# nearsens-schematic-source-2026-05-26-dra.net
KiCad netlist of a schematic drawn in EasyEDA
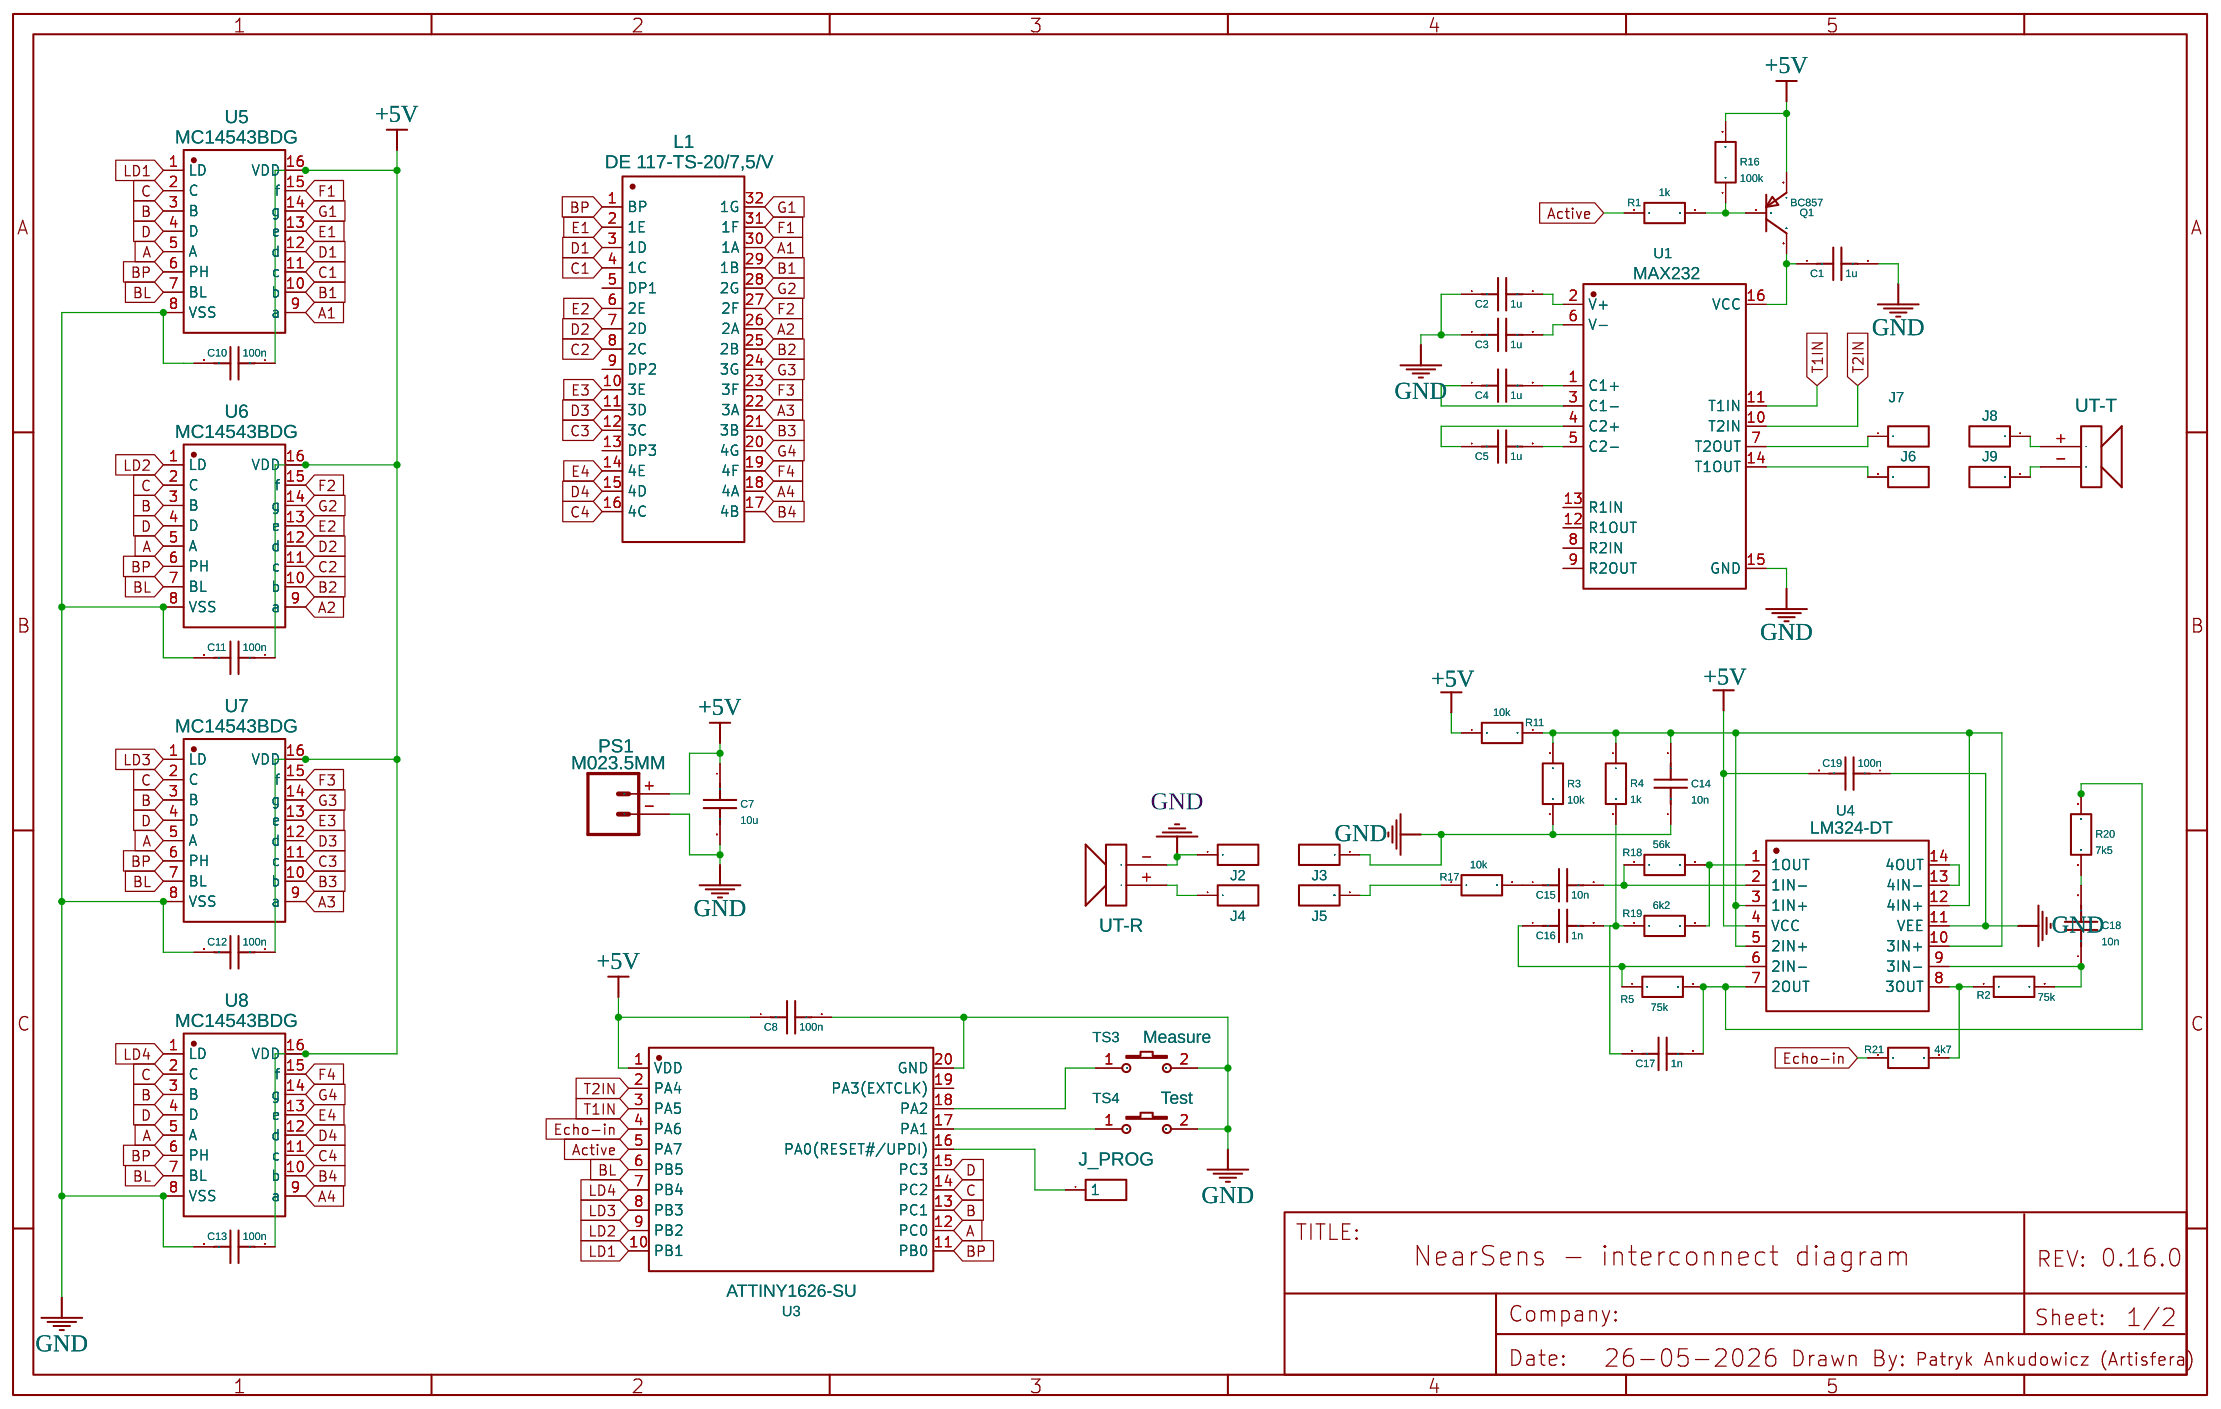
[diagram p0: schematic sheet]

(export (version "E")
  (design (tool "Eeschema 10.0.6"))
  (components
    (comp (ref "C1") (value "1u") (libsource (lib "") (part "C_0603_US")))
    (comp (ref "C2") (value "1u") (libsource (lib "") (part "C_0603_US")))
    (comp (ref "C3") (value "1u") (libsource (lib "") (part "C_0603_US")))
    (comp (ref "C4") (value "1u") (libsource (lib "") (part "C_0603_US")))
    (comp (ref "C5") (value "1u") (libsource (lib "") (part "C_0603_US")))
    (comp (ref "C7") (value "10u") (libsource (lib "") (part "C_0603_US_2")))
    (comp (ref "C8") (value "100n") (libsource (lib "") (part "C_0603_US")))
    (comp (ref "C10") (value "100n") (libsource (lib "") (part "C_0603_US_3")))
    (comp (ref "C11") (value "100n") (libsource (lib "") (part "C_0603_US_3")))
    (comp (ref "C12") (value "100n") (libsource (lib "") (part "C_0603_US_3")))
    (comp (ref "C13") (value "100n") (libsource (lib "") (part "C_0603_US_3")))
    (comp (ref "C14") (value "10n") (libsource (lib "") (part "C_0603_US_1")))
    (comp (ref "C15") (value "10n") (libsource (lib "") (part "C_0603_US")))
    (comp (ref "C16") (value "1n") (libsource (lib "") (part "C_0603_US")))
    (comp (ref "C17") (value "1n") (libsource (lib "") (part "C_0603_US")))
    (comp (ref "C18") (value "10n") (libsource (lib "") (part "C_0603_US_1")))
    (comp (ref "C19") (value "100n") (libsource (lib "") (part "C_0603_US_3")))
    (comp (ref "J2") (value "HDR-M-2.54_1x1") (libsource (lib "") (part "HDR-M-2.54_1x1_1")))
    (comp (ref "J3") (value "HDR-M-2.54_1x1") (libsource (lib "") (part "HDR-M-2.54_1x1")))
    (comp (ref "J4") (value "HDR-M-2.54_1x1") (libsource (lib "") (part "HDR-M-2.54_1x1_1")))
    (comp (ref "J5") (value "HDR-M-2.54_1x1") (libsource (lib "") (part "HDR-M-2.54_1x1_3")))
    (comp (ref "J6") (value "HDR-M-2.54_1x1") (libsource (lib "") (part "HDR-M-2.54_1x1_1")))
    (comp (ref "J7") (value "HDR-M-2.54_1x1") (libsource (lib "") (part "HDR-M-2.54_1x1_1")))
    (comp (ref "J8") (value "HDR-M-2.54_1x1") (libsource (lib "") (part "HDR-M-2.54_1x1")))
    (comp (ref "J9") (value "HDR-M-2.54_1x1") (libsource (lib "") (part "HDR-M-2.54_1x1")))
    (comp (ref "J_PROG") (value "Programming") (libsource (lib "") (part "HDR-M-2.54_1x1_2")))
    (comp (ref "L1")
      (value "DE 117-TS-20/7,5/V")
      (fields (field (name "Manufacturer") "DISPLAY ELEKTRONIK"))
      (libsource (lib "") (part "DE 117-TS-20/7,5/V DISPLAY ELEKTRONIK - Display LCD"))
    )
    (comp (ref "PS1") (value "M023.5MM") (libsource (lib "") (part "M023.5MM")))
    (comp (ref "Q1")
      (value "BC857")
      (fields
        (field (name "Manufacturer Part") "BC557(RANGE:420-800)")
        (field (name "Manufacturer") "CJ(江苏长电/长晶)")
      )
      (libsource (lib "") (part "BC557"))
    )
    (comp (ref "R1") (value "1k") (libsource (lib "") (part "R_0603_EU_1")))
    (comp (ref "R2") (value "75k") (libsource (lib "") (part "R_0603_EU_1")))
    (comp (ref "R3") (value "10k") (libsource (lib "") (part "R_0603_EU")))
    (comp (ref "R4") (value "1k") (libsource (lib "") (part "R_0603_EU_2")))
    (comp (ref "R5") (value "75k") (libsource (lib "") (part "R_0603_EU_1")))
    (comp (ref "R11") (value "10k") (libsource (lib "") (part "R_0603_EU_1")))
    (comp (ref "R16") (value "100k") (libsource (lib "") (part "R_0603_EU")))
    (comp (ref "R17") (value "10k") (libsource (lib "") (part "R_0603_EU_1")))
    (comp (ref "R18") (value "56k") (libsource (lib "") (part "R_0603_EU_1")))
    (comp (ref "R19") (value "6k2") (libsource (lib "") (part "R_0603_EU_1")))
    (comp (ref "R20") (value "7k5") (libsource (lib "") (part "R_0603_EU")))
    (comp (ref "R21") (value "4k7") (libsource (lib "") (part "R_0603_EU_1")))
    (comp (ref "TS3")
      (value "Measure")
      (fields (field (name "Manufacturer Part") "K2-1107ST-A4SW-06"))
      (libsource (lib "") (part "K2-3.6×6.1_SMD"))
    )
    (comp (ref "TS4")
      (value "Test")
      (fields (field (name "Manufacturer Part") "K2-1107ST-A4SW-06"))
      (libsource (lib "") (part "K2-3.6×6.1_SMD"))
    )
    (comp (ref "U1")
      (value "MAX232")
      (fields (field (name "Manufacturer Part") "MAX232ESE-EV") (field (name "Manufacturer") "EVVO(翊欧)"))
      (libsource (lib "") (part "MAX232ESE-EV"))
    )
    (comp (ref "U3")
      (value "ATTINY1626-SU")
      (fields (field (name "Manufacturer") "MICROCHIP(美国微芯)"))
      (libsource (lib "") (part "ATTINY1626-SU"))
    )
    (comp (ref "U4")
      (value "LM324-DT")
      (fields (field (name "Manufacturer Part") "LM324-DW") (field (name "Manufacturer") "DOWO(东沃)"))
      (libsource (lib "") (part "LM324-DW"))
    )
    (comp (ref "U5") (value "MC14543BDG") (libsource (lib "") (part "MC14543BDG")))
    (comp (ref "U6") (value "MC14543BDG") (libsource (lib "") (part "MC14543BDG")))
    (comp (ref "U7") (value "MC14543BDG") (libsource (lib "") (part "MC14543BDG")))
    (comp (ref "U8") (value "MC14543BDG") (libsource (lib "") (part "MC14543BDG")))
    (comp (ref "UT-R")
      (value "Przetwornik ultradzwiekowy")
      (fields (field (name "Manufacturer Part") "I47123") (field (name "Manufacturer") "I47"))
      (libsource (lib "") (part "ULTRASONIC TRANSDUCER_1"))
    )
    (comp (ref "UT-T")
      (value "Przetwornik ultradzwiekowy")
      (fields (field (name "Manufacturer Part") "I47123") (field (name "Manufacturer") "I47"))
      (libsource (lib "") (part "ULTRASONIC TRANSDUCER"))
    )
  )
  (nets
    (net (code "1") (name "+5V") (class "Default")
      (node (ref "C10") (pin "1") (pinfunction "1_1") (pintype "unspecified"))
      (node (ref "C11") (pin "1") (pinfunction "1_1") (pintype "unspecified"))
      (node (ref "C12") (pin "1") (pinfunction "1_1") (pintype "unspecified"))
      (node (ref "C13") (pin "1") (pinfunction "1_1") (pintype "unspecified"))
      (node (ref "C19") (pin "2") (pinfunction "2_2") (pintype "unspecified"))
      (node (ref "C7") (pin "1") (pinfunction "1_1") (pintype "unspecified"))
      (node (ref "C8") (pin "1") (pinfunction "1_1") (pintype "unspecified"))
      (node (ref "PS1") (pin "+") (pinfunction "2_+") (pintype "bidirectional"))
      (node (ref "Q1") (pin "2") (pinfunction "E_2") (pintype "unspecified"))
      (node (ref "R11") (pin "1") (pinfunction "1_1") (pintype "unspecified"))
      (node (ref "R16") (pin "2") (pinfunction "2_2") (pintype "unspecified"))
      (node (ref "U3") (pin "1") (pinfunction "VDD_1") (pintype "unspecified"))
      (node (ref "U4") (pin "4") (pinfunction "VCC_4") (pintype "unspecified"))
      (node (ref "U5") (pin "16") (pinfunction "VDD_16") (pintype "unspecified"))
      (node (ref "U6") (pin "16") (pinfunction "VDD_16") (pintype "unspecified"))
      (node (ref "U7") (pin "16") (pinfunction "VDD_16") (pintype "unspecified"))
      (node (ref "U8") (pin "16") (pinfunction "VDD_16") (pintype "unspecified"))
    )
    (net (code "2") (name "A") (class "Default")
      (node (ref "U3") (pin "12") (pinfunction "PC0_12") (pintype "unspecified"))
      (node (ref "U5") (pin "5") (pinfunction "A_5") (pintype "unspecified"))
      (node (ref "U6") (pin "5") (pinfunction "A_5") (pintype "unspecified"))
      (node (ref "U7") (pin "5") (pinfunction "A_5") (pintype "unspecified"))
      (node (ref "U8") (pin "5") (pinfunction "A_5") (pintype "unspecified"))
    )
    (net (code "3") (name "A1") (class "Default")
      (node (ref "L1") (pin "30") (pinfunction "1A_30") (pintype "unspecified"))
      (node (ref "U5") (pin "9") (pinfunction "a_9") (pintype "unspecified"))
    )
    (net (code "4") (name "A2") (class "Default")
      (node (ref "L1") (pin "26") (pinfunction "2A_26") (pintype "unspecified"))
      (node (ref "U6") (pin "9") (pinfunction "a_9") (pintype "unspecified"))
    )
    (net (code "5") (name "A3") (class "Default")
      (node (ref "L1") (pin "22") (pinfunction "3A_22") (pintype "unspecified"))
      (node (ref "U7") (pin "9") (pinfunction "a_9") (pintype "unspecified"))
    )
    (net (code "6") (name "A4") (class "Default")
      (node (ref "L1") (pin "18") (pinfunction "4A_18") (pintype "unspecified"))
      (node (ref "U8") (pin "9") (pinfunction "a_9") (pintype "unspecified"))
    )
    (net (code "7") (name "Active") (class "Default")
      (node (ref "R1") (pin "1") (pinfunction "1_1") (pintype "unspecified"))
      (node (ref "U3") (pin "5") (pinfunction "PA7_5") (pintype "unspecified"))
    )
    (net (code "8") (name "B") (class "Default")
      (node (ref "U3") (pin "13") (pinfunction "PC1_13") (pintype "unspecified"))
      (node (ref "U5") (pin "3") (pinfunction "B_3") (pintype "unspecified"))
      (node (ref "U6") (pin "3") (pinfunction "B_3") (pintype "unspecified"))
      (node (ref "U7") (pin "3") (pinfunction "B_3") (pintype "unspecified"))
      (node (ref "U8") (pin "3") (pinfunction "B_3") (pintype "unspecified"))
    )
    (net (code "9") (name "B1") (class "Default")
      (node (ref "L1") (pin "29") (pinfunction "1B_29") (pintype "unspecified"))
      (node (ref "U5") (pin "10") (pinfunction "b_10") (pintype "unspecified"))
    )
    (net (code "10") (name "B2") (class "Default")
      (node (ref "L1") (pin "25") (pinfunction "2B_25") (pintype "unspecified"))
      (node (ref "U6") (pin "10") (pinfunction "b_10") (pintype "unspecified"))
    )
    (net (code "11") (name "B3") (class "Default")
      (node (ref "L1") (pin "21") (pinfunction "3B_21") (pintype "unspecified"))
      (node (ref "U7") (pin "10") (pinfunction "b_10") (pintype "unspecified"))
    )
    (net (code "12") (name "B4") (class "Default")
      (node (ref "L1") (pin "17") (pinfunction "4B_17") (pintype "unspecified"))
      (node (ref "U8") (pin "10") (pinfunction "b_10") (pintype "unspecified"))
    )
    (net (code "13") (name "BL") (class "Default")
      (node (ref "U3") (pin "6") (pinfunction "PB5_6") (pintype "unspecified"))
      (node (ref "U5") (pin "7") (pinfunction "BL_7") (pintype "unspecified"))
      (node (ref "U6") (pin "7") (pinfunction "BL_7") (pintype "unspecified"))
      (node (ref "U7") (pin "7") (pinfunction "BL_7") (pintype "unspecified"))
      (node (ref "U8") (pin "7") (pinfunction "BL_7") (pintype "unspecified"))
    )
    (net (code "14") (name "BP") (class "Default")
      (node (ref "L1") (pin "1") (pinfunction "BP_1") (pintype "unspecified"))
      (node (ref "U3") (pin "11") (pinfunction "PB0_11") (pintype "unspecified"))
      (node (ref "U5") (pin "6") (pinfunction "PH_6") (pintype "unspecified"))
      (node (ref "U6") (pin "6") (pinfunction "PH_6") (pintype "unspecified"))
      (node (ref "U7") (pin "6") (pinfunction "PH_6") (pintype "unspecified"))
      (node (ref "U8") (pin "6") (pinfunction "PH_6") (pintype "unspecified"))
    )
    (net (code "15") (name "C") (class "Default")
      (node (ref "U3") (pin "14") (pinfunction "PC2_14") (pintype "unspecified"))
      (node (ref "U5") (pin "2") (pinfunction "C_2") (pintype "unspecified"))
      (node (ref "U6") (pin "2") (pinfunction "C_2") (pintype "unspecified"))
      (node (ref "U7") (pin "2") (pinfunction "C_2") (pintype "unspecified"))
      (node (ref "U8") (pin "2") (pinfunction "C_2") (pintype "unspecified"))
    )
    (net (code "16") (name "C1") (class "Default")
      (node (ref "L1") (pin "4") (pinfunction "1C_4") (pintype "unspecified"))
      (node (ref "U5") (pin "11") (pinfunction "c_11") (pintype "unspecified"))
    )
    (net (code "17") (name "C2") (class "Default")
      (node (ref "L1") (pin "8") (pinfunction "2C_8") (pintype "unspecified"))
      (node (ref "U6") (pin "11") (pinfunction "c_11") (pintype "unspecified"))
    )
    (net (code "18") (name "C3") (class "Default")
      (node (ref "L1") (pin "12") (pinfunction "3C_12") (pintype "unspecified"))
      (node (ref "U7") (pin "11") (pinfunction "c_11") (pintype "unspecified"))
    )
    (net (code "19") (name "C4") (class "Default")
      (node (ref "L1") (pin "16") (pinfunction "4C_16") (pintype "unspecified"))
      (node (ref "U8") (pin "11") (pinfunction "c_11") (pintype "unspecified"))
    )
    (net (code "20") (name "D") (class "Default")
      (node (ref "U3") (pin "15") (pinfunction "PC3_15") (pintype "unspecified"))
      (node (ref "U5") (pin "4") (pinfunction "D_4") (pintype "unspecified"))
      (node (ref "U6") (pin "4") (pinfunction "D_4") (pintype "unspecified"))
      (node (ref "U7") (pin "4") (pinfunction "D_4") (pintype "unspecified"))
      (node (ref "U8") (pin "4") (pinfunction "D_4") (pintype "unspecified"))
    )
    (net (code "21") (name "D1") (class "Default")
      (node (ref "L1") (pin "3") (pinfunction "1D_3") (pintype "unspecified"))
      (node (ref "U5") (pin "12") (pinfunction "d_12") (pintype "unspecified"))
    )
    (net (code "22") (name "D2") (class "Default")
      (node (ref "L1") (pin "7") (pinfunction "2D_7") (pintype "unspecified"))
      (node (ref "U6") (pin "12") (pinfunction "d_12") (pintype "unspecified"))
    )
    (net (code "23") (name "D3") (class "Default")
      (node (ref "L1") (pin "11") (pinfunction "3D_11") (pintype "unspecified"))
      (node (ref "U7") (pin "12") (pinfunction "d_12") (pintype "unspecified"))
    )
    (net (code "24") (name "D4") (class "Default")
      (node (ref "L1") (pin "15") (pinfunction "4D_15") (pintype "unspecified"))
      (node (ref "U8") (pin "12") (pinfunction "d_12") (pintype "unspecified"))
    )
    (net (code "25") (name "E1") (class "Default")
      (node (ref "L1") (pin "2") (pinfunction "1E_2") (pintype "unspecified"))
      (node (ref "U5") (pin "13") (pinfunction "e_13") (pintype "unspecified"))
    )
    (net (code "26") (name "E2") (class "Default")
      (node (ref "L1") (pin "6") (pinfunction "2E_6") (pintype "unspecified"))
      (node (ref "U6") (pin "13") (pinfunction "e_13") (pintype "unspecified"))
    )
    (net (code "27") (name "E3") (class "Default")
      (node (ref "L1") (pin "10") (pinfunction "3E_10") (pintype "unspecified"))
      (node (ref "U7") (pin "13") (pinfunction "e_13") (pintype "unspecified"))
    )
    (net (code "28") (name "E4") (class "Default")
      (node (ref "L1") (pin "14") (pinfunction "4E_14") (pintype "unspecified"))
      (node (ref "U8") (pin "13") (pinfunction "e_13") (pintype "unspecified"))
    )
    (net (code "29") (name "Echo-in") (class "Default")
      (node (ref "R21") (pin "1") (pinfunction "1_1") (pintype "unspecified"))
      (node (ref "U3") (pin "4") (pinfunction "PA6_4") (pintype "unspecified"))
    )
    (net (code "30") (name "F1") (class "Default")
      (node (ref "L1") (pin "31") (pinfunction "1F_31") (pintype "unspecified"))
      (node (ref "U5") (pin "15") (pinfunction "f_15") (pintype "unspecified"))
    )
    (net (code "31") (name "F2") (class "Default")
      (node (ref "L1") (pin "27") (pinfunction "2F_27") (pintype "unspecified"))
      (node (ref "U6") (pin "15") (pinfunction "f_15") (pintype "unspecified"))
    )
    (net (code "32") (name "F3") (class "Default")
      (node (ref "L1") (pin "23") (pinfunction "3F_23") (pintype "unspecified"))
      (node (ref "U7") (pin "15") (pinfunction "f_15") (pintype "unspecified"))
    )
    (net (code "33") (name "F4") (class "Default")
      (node (ref "L1") (pin "19") (pinfunction "4F_19") (pintype "unspecified"))
      (node (ref "U8") (pin "15") (pinfunction "f_15") (pintype "unspecified"))
    )
    (net (code "34") (name "G1") (class "Default")
      (node (ref "L1") (pin "32") (pinfunction "1G_32") (pintype "unspecified"))
      (node (ref "U5") (pin "14") (pinfunction "g_14") (pintype "unspecified"))
    )
    (net (code "35") (name "G2") (class "Default")
      (node (ref "L1") (pin "28") (pinfunction "2G_28") (pintype "unspecified"))
      (node (ref "U6") (pin "14") (pinfunction "g_14") (pintype "unspecified"))
    )
    (net (code "36") (name "G3") (class "Default")
      (node (ref "L1") (pin "24") (pinfunction "3G_24") (pintype "unspecified"))
      (node (ref "U7") (pin "14") (pinfunction "g_14") (pintype "unspecified"))
    )
    (net (code "37") (name "G4") (class "Default")
      (node (ref "L1") (pin "20") (pinfunction "4G_20") (pintype "unspecified"))
      (node (ref "U8") (pin "14") (pinfunction "g_14") (pintype "unspecified"))
    )
    (net (code "38") (name "GND") (class "Default")
      (node (ref "C1") (pin "2") (pinfunction "2_2") (pintype "unspecified"))
      (node (ref "C10") (pin "2") (pinfunction "2_2") (pintype "unspecified"))
      (node (ref "C11") (pin "2") (pinfunction "2_2") (pintype "unspecified"))
      (node (ref "C12") (pin "2") (pinfunction "2_2") (pintype "unspecified"))
      (node (ref "C13") (pin "2") (pinfunction "2_2") (pintype "unspecified"))
      (node (ref "C14") (pin "1") (pinfunction "1_1") (pintype "unspecified"))
      (node (ref "C19") (pin "1") (pinfunction "1_1") (pintype "unspecified"))
      (node (ref "C2") (pin "1") (pinfunction "1_1") (pintype "unspecified"))
      (node (ref "C3") (pin "1") (pinfunction "1_1") (pintype "unspecified"))
      (node (ref "C7") (pin "2") (pinfunction "2_2") (pintype "unspecified"))
      (node (ref "C8") (pin "2") (pinfunction "2_2") (pintype "unspecified"))
      (node (ref "J2") (pin "1") (pinfunction "1_1") (pintype "input"))
      (node (ref "J3") (pin "1") (pinfunction "1_1") (pintype "input"))
      (node (ref "PS1") (pin "-") (pinfunction "1_-") (pintype "bidirectional"))
      (node (ref "R3") (pin "1") (pinfunction "1_1") (pintype "unspecified"))
      (node (ref "TS3") (pin "2") (pinfunction "2_2") (pintype "unspecified"))
      (node (ref "TS4") (pin "2") (pinfunction "2_2") (pintype "unspecified"))
      (node (ref "U1") (pin "15") (pinfunction "GND_15") (pintype "unspecified"))
      (node (ref "U3") (pin "20") (pinfunction "GND_20") (pintype "unspecified"))
      (node (ref "U4") (pin "11") (pinfunction "VEE_11") (pintype "unspecified"))
      (node (ref "U5") (pin "8") (pinfunction "VSS_8") (pintype "unspecified"))
      (node (ref "U6") (pin "8") (pinfunction "VSS_8") (pintype "unspecified"))
      (node (ref "U7") (pin "8") (pinfunction "VSS_8") (pintype "unspecified"))
      (node (ref "U8") (pin "8") (pinfunction "VSS_8") (pintype "unspecified"))
      (node (ref "UT-R") (pin "-") (pinfunction "+_-") (pintype "bidirectional"))
    )
    (net (code "39") (name "LD1") (class "Default")
      (node (ref "U3") (pin "10") (pinfunction "PB1_10") (pintype "unspecified"))
      (node (ref "U5") (pin "1") (pinfunction "LD_1") (pintype "unspecified"))
    )
    (net (code "40") (name "LD2") (class "Default")
      (node (ref "U3") (pin "9") (pinfunction "PB2_9") (pintype "unspecified"))
      (node (ref "U6") (pin "1") (pinfunction "LD_1") (pintype "unspecified"))
    )
    (net (code "41") (name "LD3") (class "Default")
      (node (ref "U3") (pin "8") (pinfunction "PB3_8") (pintype "unspecified"))
      (node (ref "U7") (pin "1") (pinfunction "LD_1") (pintype "unspecified"))
    )
    (net (code "42") (name "LD4") (class "Default")
      (node (ref "U3") (pin "7") (pinfunction "PB4_7") (pintype "unspecified"))
      (node (ref "U8") (pin "1") (pinfunction "LD_1") (pintype "unspecified"))
    )
    (net (code "43") (name "Net-(C15-Pad1)") (class "Default")
      (node (ref "C15") (pin "1") (pinfunction "1_1") (pintype "unspecified"))
      (node (ref "R17") (pin "2") (pinfunction "2_2") (pintype "unspecified"))
    )
    (net (code "44") (name "Net-(C16-Pad2)") (class "Default")
      (node (ref "C16") (pin "2") (pinfunction "2_2") (pintype "unspecified"))
      (node (ref "C17") (pin "1") (pinfunction "1_1") (pintype "unspecified"))
      (node (ref "R19") (pin "1") (pinfunction "1_1") (pintype "unspecified"))
      (node (ref "R4") (pin "2") (pinfunction "2_2") (pintype "unspecified"))
    )
    (net (code "45") (name "Net-(C18-Pad2)") (class "Default")
      (node (ref "C18") (pin "2") (pinfunction "2_2") (pintype "unspecified"))
      (node (ref "R20") (pin "1") (pinfunction "1_1") (pintype "unspecified"))
    )
    (net (code "46") (name "Net-(J5-PAD)") (class "Default")
      (node (ref "J5") (pin "1") (pinfunction "PAD_1") (pintype "input"))
      (node (ref "R17") (pin "1") (pinfunction "1_1") (pintype "unspecified"))
    )
    (net (code "47") (name "Net-(Q1-B)") (class "Default")
      (node (ref "Q1") (pin "1") (pinfunction "B_1") (pintype "unspecified"))
      (node (ref "R1") (pin "2") (pinfunction "2_2") (pintype "unspecified"))
      (node (ref "R16") (pin "1") (pinfunction "1_1") (pintype "unspecified"))
    )
    (net (code "48") (name "Net-(Q1-C)") (class "Default")
      (node (ref "C1") (pin "1") (pinfunction "1_1") (pintype "unspecified"))
      (node (ref "Q1") (pin "3") (pinfunction "C_3") (pintype "unspecified"))
      (node (ref "U1") (pin "16") (pinfunction "VCC_16") (pintype "unspecified"))
    )
    (net (code "49") (name "Net-(U1-C1+)") (class "Default")
      (node (ref "C4") (pin "2") (pinfunction "2_2") (pintype "unspecified"))
      (node (ref "U1") (pin "1") (pinfunction "C1+_1") (pintype "unspecified"))
    )
    (net (code "50") (name "Net-(U1-C1-)") (class "Default")
      (node (ref "C4") (pin "1") (pinfunction "1_1") (pintype "unspecified"))
      (node (ref "U1") (pin "3") (pinfunction "C1-_3") (pintype "unspecified"))
    )
    (net (code "51") (name "Net-(U1-C2+)") (class "Default")
      (node (ref "C5") (pin "1") (pinfunction "1_1") (pintype "unspecified"))
      (node (ref "U1") (pin "4") (pinfunction "C2+_4") (pintype "unspecified"))
    )
    (net (code "52") (name "Net-(U1-C2-)") (class "Default")
      (node (ref "C5") (pin "2") (pinfunction "2_2") (pintype "unspecified"))
      (node (ref "U1") (pin "5") (pinfunction "C2-_5") (pintype "unspecified"))
    )
    (net (code "53") (name "Net-(U1-T1OUT)") (class "Default")
      (node (ref "J6") (pin "1") (pinfunction "1_1") (pintype "input"))
      (node (ref "U1") (pin "14") (pinfunction "T1OUT_14") (pintype "unspecified"))
    )
    (net (code "54") (name "Net-(U1-T2OUT)") (class "Default")
      (node (ref "J7") (pin "1") (pinfunction "1_1") (pintype "input"))
      (node (ref "U1") (pin "7") (pinfunction "T2OUT_7") (pintype "unspecified"))
    )
    (net (code "55") (name "Net-(U1-V+)") (class "Default")
      (node (ref "C2") (pin "2") (pinfunction "2_2") (pintype "unspecified"))
      (node (ref "U1") (pin "2") (pinfunction "V+_2") (pintype "unspecified"))
    )
    (net (code "56") (name "Net-(U1-V-)") (class "Default")
      (node (ref "C3") (pin "2") (pinfunction "2_2") (pintype "unspecified"))
      (node (ref "U1") (pin "6") (pinfunction "V-_6") (pintype "unspecified"))
    )
    (net (code "57") (name "Net-(U3-PA0(RESET#{slash}UPDI))") (class "Default")
      (node (ref "J_PROG") (pin "1") (pinfunction "1_1") (pintype "input"))
      (node (ref "U3") (pin "16") (pinfunction "PA0(RESET#/UPDI)_16") (pintype "unspecified"))
    )
    (net (code "58") (name "Net-(U3-PA1)") (class "Default")
      (node (ref "TS4") (pin "1") (pinfunction "1_1") (pintype "unspecified"))
      (node (ref "U3") (pin "17") (pinfunction "PA1_17") (pintype "unspecified"))
    )
    (net (code "59") (name "Net-(U3-PA2)") (class "Default")
      (node (ref "TS3") (pin "1") (pinfunction "1_1") (pintype "unspecified"))
      (node (ref "U3") (pin "18") (pinfunction "PA2_18") (pintype "unspecified"))
    )
    (net (code "60") (name "Net-(U4-1IN+)") (class "Default")
      (node (ref "C14") (pin "2") (pinfunction "2_2") (pintype "unspecified"))
      (node (ref "R11") (pin "2") (pinfunction "2_2") (pintype "unspecified"))
      (node (ref "R3") (pin "2") (pinfunction "2_2") (pintype "unspecified"))
      (node (ref "R4") (pin "1") (pinfunction "1_1") (pintype "unspecified"))
      (node (ref "U4") (pin "10") (pinfunction "3IN+_10") (pintype "unspecified"))
      (node (ref "U4") (pin "12") (pinfunction "4IN+_12") (pintype "unspecified"))
      (node (ref "U4") (pin "3") (pinfunction "1IN+_3") (pintype "unspecified"))
      (node (ref "U4") (pin "5") (pinfunction "2IN+_5") (pintype "unspecified"))
    )
    (net (code "61") (name "Net-(U4-1IN-)") (class "Default")
      (node (ref "C15") (pin "2") (pinfunction "2_2") (pintype "unspecified"))
      (node (ref "R18") (pin "1") (pinfunction "1_1") (pintype "unspecified"))
      (node (ref "U4") (pin "2") (pinfunction "1IN-_2") (pintype "unspecified"))
    )
    (net (code "62") (name "Net-(U4-1OUT)") (class "Default")
      (node (ref "R18") (pin "2") (pinfunction "2_2") (pintype "unspecified"))
      (node (ref "R19") (pin "2") (pinfunction "2_2") (pintype "unspecified"))
      (node (ref "U4") (pin "1") (pinfunction "1OUT_1") (pintype "unspecified"))
    )
    (net (code "63") (name "Net-(U4-2IN-)") (class "Default")
      (node (ref "C16") (pin "1") (pinfunction "1_1") (pintype "unspecified"))
      (node (ref "R5") (pin "1") (pinfunction "1_1") (pintype "unspecified"))
      (node (ref "U4") (pin "6") (pinfunction "2IN-_6") (pintype "unspecified"))
    )
    (net (code "64") (name "Net-(U4-2OUT)") (class "Default")
      (node (ref "C17") (pin "2") (pinfunction "2_2") (pintype "unspecified"))
      (node (ref "R20") (pin "2") (pinfunction "2_2") (pintype "unspecified"))
      (node (ref "R5") (pin "2") (pinfunction "2_2") (pintype "unspecified"))
      (node (ref "U4") (pin "7") (pinfunction "2OUT_7") (pintype "unspecified"))
    )
    (net (code "65") (name "Net-(U4-3IN-)") (class "Default")
      (node (ref "C18") (pin "1") (pinfunction "1_1") (pintype "unspecified"))
      (node (ref "R2") (pin "2") (pinfunction "2_2") (pintype "unspecified"))
      (node (ref "U4") (pin "9") (pinfunction "3IN-_9") (pintype "unspecified"))
    )
    (net (code "66") (name "Net-(U4-3OUT)") (class "Default")
      (node (ref "R2") (pin "1") (pinfunction "1_1") (pintype "unspecified"))
      (node (ref "R21") (pin "2") (pinfunction "2_2") (pintype "unspecified"))
      (node (ref "U4") (pin "8") (pinfunction "3OUT_8") (pintype "unspecified"))
    )
    (net (code "67") (name "Net-(U4-4IN-)") (class "Default")
      (node (ref "U4") (pin "13") (pinfunction "4IN-_13") (pintype "unspecified"))
      (node (ref "U4") (pin "14") (pinfunction "4OUT_14") (pintype "unspecified"))
    )
    (net (code "68") (name "Net-(UT-R--)") (class "Default")
      (node (ref "J4") (pin "1") (pinfunction "1_1") (pintype "input"))
      (node (ref "UT-R") (pin "+") (pinfunction "-_+") (pintype "bidirectional"))
    )
    (net (code "69") (name "Net-(UT-T-+)") (class "Default")
      (node (ref "J9") (pin "1") (pinfunction "1_1") (pintype "input"))
      (node (ref "UT-T") (pin "-") (pinfunction "+_-") (pintype "bidirectional"))
    )
    (net (code "70") (name "Net-(UT-T--)") (class "Default")
      (node (ref "J8") (pin "1") (pinfunction "1_1") (pintype "input"))
      (node (ref "UT-T") (pin "+") (pinfunction "-_+") (pintype "bidirectional"))
    )
    (net (code "71") (name "T1IN") (class "Default")
      (node (ref "U1") (pin "11") (pinfunction "T1IN_11") (pintype "unspecified"))
      (node (ref "U3") (pin "3") (pinfunction "PA5_3") (pintype "unspecified"))
    )
    (net (code "72") (name "T2IN") (class "Default")
      (node (ref "U1") (pin "10") (pinfunction "T2IN_10") (pintype "unspecified"))
      (node (ref "U3") (pin "2") (pinfunction "PA4_2") (pintype "unspecified"))
    )
    (net (code "73") (name "unconnected-(L1-DP1-Pad5)") (class "Default")
      (node (ref "L1") (pin "5") (pinfunction "DP1_5") (pintype "unspecified"))
    )
    (net (code "74") (name "unconnected-(L1-DP2-Pad9)") (class "Default")
      (node (ref "L1") (pin "9") (pinfunction "DP2_9") (pintype "unspecified"))
    )
    (net (code "75") (name "unconnected-(L1-DP3-Pad13)") (class "Default")
      (node (ref "L1") (pin "13") (pinfunction "DP3_13") (pintype "unspecified"))
    )
    (net (code "76") (name "unconnected-(U1-R1IN-Pad13)") (class "Default")
      (node (ref "U1") (pin "13") (pinfunction "R1IN_13") (pintype "unspecified"))
    )
    (net (code "77") (name "unconnected-(U1-R1OUT-Pad12)") (class "Default")
      (node (ref "U1") (pin "12") (pinfunction "R1OUT_12") (pintype "unspecified"))
    )
    (net (code "78") (name "unconnected-(U1-R2IN-Pad8)") (class "Default")
      (node (ref "U1") (pin "8") (pinfunction "R2IN_8") (pintype "unspecified"))
    )
    (net (code "79") (name "unconnected-(U1-R2OUT-Pad9)") (class "Default")
      (node (ref "U1") (pin "9") (pinfunction "R2OUT_9") (pintype "unspecified"))
    )
    (net (code "80") (name "unconnected-(U3-PA3(EXTCLK)-Pad19)") (class "Default")
      (node (ref "U3") (pin "19") (pinfunction "PA3(EXTCLK)_19") (pintype "unspecified"))
    )
  )
)
